# ADC_USB.net
KiCad netlist of a schematic drawn in Altium Designer
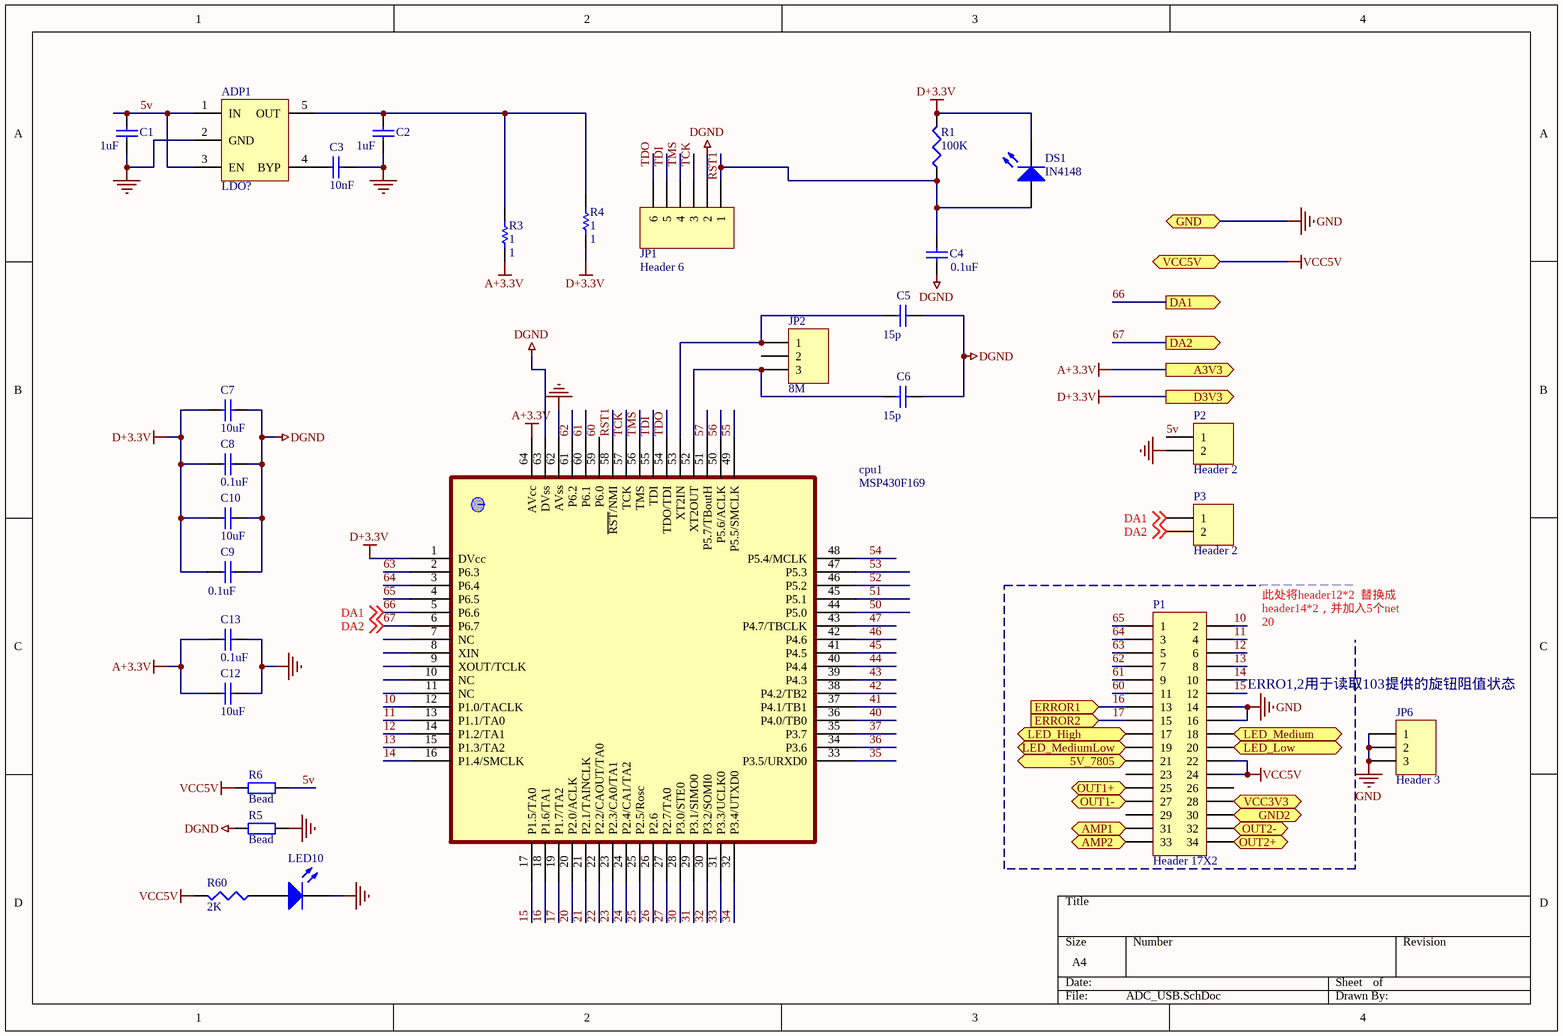
[diagram p0: ADC_USB.SchDoc]

(export (version "E")
  (design (tool "Eeschema 10.0.6"))
  (components
    (comp (ref "ADP1")
      (value "LDO?")
      (footprint "ADP1711_3v3")
      (libsource (lib "LDOlibrary") (part "ADP1711_3v3"))
    )
    (comp (ref "C1")
      (value "1uF")
      (footprint "CC1608-0603")
      (description "Capacitor (Semiconductor SIM Model)")
      (fields (field (name "Comment") "1u") (field (name "PUBLISHER") "Altium Limited"))
      (libsource (lib "Miscellaneous Devices") (part "Cap Semi"))
    )
    (comp (ref "C2")
      (value "1uF")
      (footprint "CC1608-0603")
      (description "Capacitor (Semiconductor SIM Model)")
      (fields (field (name "Comment") "1u") (field (name "PUBLISHER") "Altium Limited"))
      (libsource (lib "Miscellaneous Devices") (part "Cap Semi"))
    )
    (comp (ref "C3")
      (value "10nF")
      (footprint "CC1608-0603")
      (description "Capacitor (Semiconductor SIM Model)")
      (fields (field (name "Comment") "10n") (field (name "PUBLISHER") "Altium Limited"))
      (libsource (lib "Miscellaneous Devices") (part "Cap Semi"))
    )
    (comp (ref "C4")
      (value "0.1uF")
      (footprint "CC1608-0603")
      (description "Capacitor (Semiconductor SIM Model)")
      (fields (field (name "PUBLISHER") "Altium Limited"))
      (libsource (lib "LAN_server") (part "Cap Semi"))
    )
    (comp (ref "C5")
      (value "15p")
      (footprint "CC1608-0603")
      (description "Capacitor (Semiconductor SIM Model)")
      (fields (field (name "PUBLISHER") "Altium Limited"))
      (libsource (lib "LAN_server") (part "Cap Semi"))
    )
    (comp (ref "C6")
      (value "15p")
      (footprint "CC1608-0603")
      (description "Capacitor (Semiconductor SIM Model)")
      (fields (field (name "PUBLISHER") "Altium Limited"))
      (libsource (lib "LAN_server") (part "Cap Semi"))
    )
    (comp (ref "C7")
      (value "10uF")
      (footprint "CC3216-1206")
      (description "Capacitor (Semiconductor SIM Model)")
      (fields (field (name "PUBLISHER") "Altium Limited"))
      (libsource (lib "LAN_server") (part "Cap Semi"))
    )
    (comp (ref "C8")
      (value "0.1uF")
      (footprint "CC1608-0603")
      (description "Capacitor (Semiconductor SIM Model)")
      (fields (field (name "Comment") "Cap Semi") (field (name "PUBLISHER") "Altium Limited"))
      (libsource (lib "LAN_server") (part "Cap Semi"))
    )
    (comp (ref "C9")
      (value "0.1uF")
      (footprint "CC1608-0603")
      (description "Capacitor (Semiconductor SIM Model)")
      (fields (field (name "PUBLISHER") "Altium Limited"))
      (libsource (lib "LAN_server") (part "Cap Semi"))
    )
    (comp (ref "C10")
      (value "10uF")
      (footprint "CC3216-1206")
      (description "Capacitor (Semiconductor SIM Model)")
      (fields (field (name "PUBLISHER") "Altium Limited"))
      (libsource (lib "LAN_server") (part "Cap Semi"))
    )
    (comp (ref "C12")
      (value "10uF")
      (footprint "CC3216-1206")
      (description "Capacitor (Semiconductor SIM Model)")
      (fields (field (name "PUBLISHER") "Altium Limited"))
      (libsource (lib "LAN_server") (part "Cap Semi"))
    )
    (comp (ref "C13")
      (value "0.1uF")
      (footprint "CC1608-0603")
      (description "Capacitor (Semiconductor SIM Model)")
      (fields (field (name "PUBLISHER") "Altium Limited"))
      (libsource (lib "LAN_server") (part "Cap Semi"))
    )
    (comp (ref "cpu1")
      (value "MSP430F169")
      (footprint "msp430f149")
      (libsource (lib "msp430f149") (part "MSP430F149"))
    )
    (comp (ref "DS1")
      (value "IN4148")
      (footprint "SMD _LED")
      (description "Typical BLUE SiC LED")
      (fields (field (name "PUBLISHER") "Altium Limited"))
      (libsource (lib "Miscellaneous Devices") (part "LED3"))
    )
    (comp (ref "JP1")
      (value "Header 6")
      (footprint "HDR1X6")
      (description "Header, 6-Pin")
      (fields (field (name "PUBLISHER") "Altium Limited"))
      (libsource (lib "Miscellaneous Connectors") (part "Header 6"))
    )
    (comp (ref "JP2")
      (value "8M")
      (footprint "HDR1X3")
      (description "Header, 3-Pin")
      (fields (field (name "PUBLISHER") "Altium Limited"))
      (libsource (lib "Miscellaneous Connectors") (part "Header 3"))
    )
    (comp (ref "JP6")
      (value "Header 3")
      (footprint "HDR1X3")
      (description "Header, 3-Pin")
      (fields (field (name "PUBLISHER") "Altium Limited"))
      (libsource (lib "Miscellaneous Connectors") (part "Header 3"))
    )
    (comp (ref "LED10")
      (value "LED")
      (footprint "6-0805_M")
      (description "Typical BLUE SiC LED")
      (fields (field (name "PUBLISHER") "Altium Limited"))
      (libsource (lib "Miscellaneous Devices") (part "LED3"))
    )
    (comp (ref "P1")
      (value "Header 17X2")
      (footprint "HDR2X17-NIUJIAO")
      (description "Header, 17-Pin, Dual row")
      (fields (field (name "PUBLISHER") "Altium Limited"))
      (libsource (lib "Miscellaneous Connectors") (part "Header 17X2"))
    )
    (comp (ref "P2")
      (value "Header 2")
      (footprint "HDR1X2")
      (description "Header, 2-Pin")
      (fields (field (name "PUBLISHER") "Altium Limited"))
      (libsource (lib "Miscellaneous Connectors") (part "Header 2"))
    )
    (comp (ref "P3")
      (value "Header 2")
      (footprint "HDR1X2")
      (description "Header, 2-Pin")
      (fields (field (name "PUBLISHER") "Altium Limited"))
      (libsource (lib "Miscellaneous Connectors") (part "Header 2"))
    )
    (comp (ref "R1")
      (value "100K")
      (footprint "C1608-0603")
      (description "Resistor")
      (fields (field (name "PUBLISHER") "Altium Limited"))
      (libsource (lib "LAN_server") (part "Res3"))
    )
    (comp (ref "R3")
      (value "1")
      (footprint "6-0805_M")
      (description "Semiconductor Resistor")
      (fields (field (name "ALTIUM_VALUE") "1") (field (name "PUBLISHER") "Altium Limited"))
      (libsource (lib "Miscellaneous Devices") (part "Res Semi"))
    )
    (comp (ref "R4")
      (value "1")
      (footprint "6-0805_M")
      (description "Semiconductor Resistor")
      (fields (field (name "ALTIUM_VALUE") "1") (field (name "PUBLISHER") "Altium Limited"))
      (libsource (lib "Miscellaneous Devices") (part "Res Semi"))
    )
    (comp (ref "R5")
      (value "Bead")
      (footprint "6-0805_M")
      (description "Resistor")
      (fields (field (name "PUBLISHER") "Altium Limited"))
      (libsource (lib "") (part "Res2_1"))
    )
    (comp (ref "R6")
      (value "Bead")
      (footprint "6-0805_M")
      (description "Resistor")
      (fields (field (name "PUBLISHER") "Altium Limited"))
      (libsource (lib "Miscellaneous Devices") (part "Res2"))
    )
    (comp (ref "R60")
      (value "2K")
      (footprint "1608[0603]")
      (description "Resistor")
      (fields (field (name "PUBLISHER") "Altium Limited"))
      (libsource (lib "LAN_server") (part "Res3"))
    )
  )
  (nets
    (net (code "1") (name "/5V_7805") (class "Default")
      (node (ref "P1") (pin "21") (pinfunction "21_21") (pintype "passive"))
    )
    (net (code "2") (name "/5v") (class "Default")
      (node (ref "ADP1") (pin "1") (pinfunction "IN_1") (pintype "passive"))
      (node (ref "ADP1") (pin "3") (pinfunction "EN_3") (pintype "passive"))
      (node (ref "C1") (pin "1") (pinfunction "1_1") (pintype "passive"))
      (node (ref "P2") (pin "1") (pinfunction "1_1") (pintype "passive"))
      (node (ref "R6") (pin "1") (pinfunction "1_1") (pintype "passive"))
    )
    (net (code "3") (name "/10") (class "Default")
      (node (ref "P1") (pin "2") (pinfunction "2_2") (pintype "passive"))
      (node (ref "cpu1") (pin "12") (pinfunction "P1.0/TACLK_12") (pintype "passive"))
    )
    (net (code "4") (name "/11") (class "Default")
      (node (ref "P1") (pin "4") (pinfunction "4_4") (pintype "passive"))
      (node (ref "cpu1") (pin "13") (pinfunction "P1.1/TA0_13") (pintype "passive"))
    )
    (net (code "5") (name "/12") (class "Default")
      (node (ref "P1") (pin "6") (pinfunction "6_6") (pintype "passive"))
      (node (ref "cpu1") (pin "14") (pinfunction "P1.2/TA1_14") (pintype "passive"))
    )
    (net (code "6") (name "/13") (class "Default")
      (node (ref "P1") (pin "8") (pinfunction "8_8") (pintype "passive"))
      (node (ref "cpu1") (pin "15") (pinfunction "P1.3/TA2_15") (pintype "passive"))
    )
    (net (code "7") (name "/14") (class "Default")
      (node (ref "P1") (pin "10") (pinfunction "10_10") (pintype "passive"))
      (node (ref "cpu1") (pin "16") (pinfunction "P1.4/SMCLK_16") (pintype "passive"))
    )
    (net (code "8") (name "/15") (class "Default")
      (node (ref "P1") (pin "12") (pinfunction "12_12") (pintype "passive"))
      (node (ref "cpu1") (pin "17") (pinfunction "P1.5/TA0_17") (pintype "passive"))
    )
    (net (code "9") (name "/16") (class "Default")
      (node (ref "P1") (pin "13") (pinfunction "13_13") (pintype "passive"))
      (node (ref "cpu1") (pin "18") (pinfunction "P1.6/TA1_18") (pintype "passive"))
    )
    (net (code "10") (name "/17") (class "Default")
      (node (ref "P1") (pin "15") (pinfunction "15_15") (pintype "passive"))
      (node (ref "cpu1") (pin "19") (pinfunction "P1.7/TA2_19") (pintype "passive"))
    )
    (net (code "11") (name "/20") (class "Default")
      (node (ref "cpu1") (pin "20") (pinfunction "P2.0/ACLK_20") (pintype "passive"))
    )
    (net (code "12") (name "/21") (class "Default")
      (node (ref "cpu1") (pin "21") (pinfunction "P2.1/TAINCLK_21") (pintype "passive"))
    )
    (net (code "13") (name "/22") (class "Default")
      (node (ref "cpu1") (pin "22") (pinfunction "P2.2/CAOUT/TA0_22") (pintype "passive"))
    )
    (net (code "14") (name "/23") (class "Default")
      (node (ref "cpu1") (pin "23") (pinfunction "P2.3/CA0/TA1_23") (pintype "passive"))
    )
    (net (code "15") (name "/24") (class "Default")
      (node (ref "cpu1") (pin "24") (pinfunction "P2.4/CA1/TA2_24") (pintype "passive"))
    )
    (net (code "16") (name "/25") (class "Default")
      (node (ref "cpu1") (pin "25") (pinfunction "P2.5/Rosc_25") (pintype "passive"))
    )
    (net (code "17") (name "/26") (class "Default")
      (node (ref "cpu1") (pin "26") (pinfunction "P2.6_26") (pintype "passive"))
    )
    (net (code "18") (name "/27") (class "Default")
      (node (ref "cpu1") (pin "27") (pinfunction "P2.7/TA0_27") (pintype "passive"))
    )
    (net (code "19") (name "/30") (class "Default")
      (node (ref "cpu1") (pin "28") (pinfunction "P3.0/STE0_28") (pintype "passive"))
    )
    (net (code "20") (name "/31") (class "Default")
      (node (ref "cpu1") (pin "29") (pinfunction "P3.1/SIMO0_29") (pintype "passive"))
    )
    (net (code "21") (name "/32") (class "Default")
      (node (ref "cpu1") (pin "30") (pinfunction "P3.2/SOMI0_30") (pintype "passive"))
    )
    (net (code "22") (name "/33") (class "Default")
      (node (ref "cpu1") (pin "31") (pinfunction "P3.3/UCLK0_31") (pintype "passive"))
    )
    (net (code "23") (name "/34") (class "Default")
      (node (ref "cpu1") (pin "32") (pinfunction "P3.4/UTXD0_32") (pintype "passive"))
    )
    (net (code "24") (name "/35") (class "Default")
      (node (ref "cpu1") (pin "33") (pinfunction "P3.5/URXD0_33") (pintype "passive"))
    )
    (net (code "25") (name "/36") (class "Default")
      (node (ref "cpu1") (pin "34") (pinfunction "P3.6_34") (pintype "passive"))
    )
    (net (code "26") (name "/37") (class "Default")
      (node (ref "cpu1") (pin "35") (pinfunction "P3.7_35") (pintype "passive"))
    )
    (net (code "27") (name "/40") (class "Default")
      (node (ref "cpu1") (pin "36") (pinfunction "P4.0/TB0_36") (pintype "passive"))
    )
    (net (code "28") (name "/41") (class "Default")
      (node (ref "cpu1") (pin "37") (pinfunction "P4.1/TB1_37") (pintype "passive"))
    )
    (net (code "29") (name "/42") (class "Default")
      (node (ref "cpu1") (pin "38") (pinfunction "P4.2/TB2_38") (pintype "passive"))
    )
    (net (code "30") (name "/43") (class "Default")
      (node (ref "cpu1") (pin "39") (pinfunction "P4.3_39") (pintype "passive"))
    )
    (net (code "31") (name "/44") (class "Default")
      (node (ref "cpu1") (pin "40") (pinfunction "P4.4_40") (pintype "passive"))
    )
    (net (code "32") (name "/45") (class "Default")
      (node (ref "cpu1") (pin "41") (pinfunction "P4.5_41") (pintype "passive"))
    )
    (net (code "33") (name "/46") (class "Default")
      (node (ref "cpu1") (pin "42") (pinfunction "P4.6_42") (pintype "passive"))
    )
    (net (code "34") (name "/47") (class "Default")
      (node (ref "cpu1") (pin "43") (pinfunction "P4.7/TBCLK_43") (pintype "passive"))
    )
    (net (code "35") (name "/50") (class "Default")
      (node (ref "cpu1") (pin "44") (pinfunction "P5.0_44") (pintype "passive"))
    )
    (net (code "36") (name "/51") (class "Default")
      (node (ref "cpu1") (pin "45") (pinfunction "P5.1_45") (pintype "passive"))
    )
    (net (code "37") (name "/52") (class "Default")
      (node (ref "cpu1") (pin "46") (pinfunction "P5.2_46") (pintype "passive"))
    )
    (net (code "38") (name "/53") (class "Default")
      (node (ref "cpu1") (pin "47") (pinfunction "P5.3_47") (pintype "passive"))
    )
    (net (code "39") (name "/54") (class "Default")
      (node (ref "cpu1") (pin "48") (pinfunction "P5.4/MCLK_48") (pintype "passive"))
    )
    (net (code "40") (name "/55") (class "Default")
      (node (ref "cpu1") (pin "49") (pinfunction "P5.5/SMCLK_49") (pintype "passive"))
    )
    (net (code "41") (name "/56") (class "Default")
      (node (ref "cpu1") (pin "50") (pinfunction "P5.6/ACLK_50") (pintype "passive"))
    )
    (net (code "42") (name "/57") (class "Default")
      (node (ref "cpu1") (pin "51") (pinfunction "P5.7/TBoutH_51") (pintype "passive"))
    )
    (net (code "43") (name "/60") (class "Default")
      (node (ref "P1") (pin "11") (pinfunction "11_11") (pintype "passive"))
      (node (ref "cpu1") (pin "59") (pinfunction "P6.0_59") (pintype "passive"))
    )
    (net (code "44") (name "/61") (class "Default")
      (node (ref "P1") (pin "9") (pinfunction "9_9") (pintype "passive"))
      (node (ref "cpu1") (pin "60") (pinfunction "P6.1_60") (pintype "passive"))
    )
    (net (code "45") (name "/62") (class "Default")
      (node (ref "P1") (pin "7") (pinfunction "7_7") (pintype "passive"))
      (node (ref "cpu1") (pin "61") (pinfunction "P6.2_61") (pintype "passive"))
    )
    (net (code "46") (name "/63") (class "Default")
      (node (ref "P1") (pin "5") (pinfunction "5_5") (pintype "passive"))
      (node (ref "cpu1") (pin "2") (pinfunction "P6.3_2") (pintype "passive"))
    )
    (net (code "47") (name "/64") (class "Default")
      (node (ref "P1") (pin "3") (pinfunction "3_3") (pintype "passive"))
      (node (ref "cpu1") (pin "3") (pinfunction "P6.4_3") (pintype "passive"))
    )
    (net (code "48") (name "/65") (class "Default")
      (node (ref "P1") (pin "1") (pinfunction "1_1") (pintype "passive"))
      (node (ref "cpu1") (pin "4") (pinfunction "P6.5_4") (pintype "passive"))
    )
    (net (code "49") (name "/AMP1") (class "Default")
      (node (ref "P1") (pin "31") (pinfunction "31_31") (pintype "passive"))
    )
    (net (code "50") (name "/AMP2") (class "Default")
      (node (ref "P1") (pin "33") (pinfunction "33_33") (pintype "passive"))
    )
    (net (code "51") (name "/GND2") (class "Default")
      (node (ref "P1") (pin "30") (pinfunction "30_30") (pintype "passive"))
    )
    (net (code "52") (name "/LED_High") (class "Default")
      (node (ref "P1") (pin "17") (pinfunction "17_17") (pintype "passive"))
    )
    (net (code "53") (name "/LED_Low") (class "Default")
      (node (ref "P1") (pin "20") (pinfunction "20_20") (pintype "passive"))
    )
    (net (code "54") (name "/LED_Medium") (class "Default")
      (node (ref "P1") (pin "18") (pinfunction "18_18") (pintype "passive"))
    )
    (net (code "55") (name "/LED_MediumLow") (class "Default")
      (node (ref "P1") (pin "19") (pinfunction "19_19") (pintype "passive"))
    )
    (net (code "56") (name "/OUT1+") (class "Default")
      (node (ref "P1") (pin "25") (pinfunction "25_25") (pintype "passive"))
    )
    (net (code "57") (name "/OUT1-") (class "Default")
      (node (ref "P1") (pin "27") (pinfunction "27_27") (pintype "passive"))
    )
    (net (code "58") (name "/OUT2+") (class "Default")
      (node (ref "P1") (pin "34") (pinfunction "34_34") (pintype "passive"))
    )
    (net (code "59") (name "/OUT2-") (class "Default")
      (node (ref "P1") (pin "32") (pinfunction "32_32") (pintype "passive"))
    )
    (net (code "60") (name "/RST1") (class "Default")
      (node (ref "C4") (pin "2") (pinfunction "2_2") (pintype "passive"))
      (node (ref "DS1") (pin "1") (pinfunction "A_1") (pintype "passive"))
      (node (ref "JP1") (pin "1") (pinfunction "1_1") (pintype "passive"))
      (node (ref "R1") (pin "1") (pinfunction "1_1") (pintype "passive"))
      (node (ref "cpu1") (pin "58") (pinfunction "~{RST}/NMI_58") (pintype "passive"))
    )
    (net (code "61") (name "/TCK") (class "Default")
      (node (ref "JP1") (pin "3") (pinfunction "3_3") (pintype "passive"))
      (node (ref "cpu1") (pin "57") (pinfunction "TCK_57") (pintype "passive"))
    )
    (net (code "62") (name "/TDI") (class "Default")
      (node (ref "JP1") (pin "5") (pinfunction "5_5") (pintype "passive"))
      (node (ref "cpu1") (pin "55") (pinfunction "TDI_55") (pintype "passive"))
    )
    (net (code "63") (name "/TDO") (class "Default")
      (node (ref "JP1") (pin "6") (pinfunction "6_6") (pintype "passive"))
      (node (ref "cpu1") (pin "54") (pinfunction "TDO/TDI_54") (pintype "passive"))
    )
    (net (code "64") (name "/TMS") (class "Default")
      (node (ref "JP1") (pin "4") (pinfunction "4_4") (pintype "passive"))
      (node (ref "cpu1") (pin "56") (pinfunction "TMS_56") (pintype "passive"))
    )
    (net (code "65") (name "/VCC3V3") (class "Default")
      (node (ref "P1") (pin "28") (pinfunction "28_28") (pintype "passive"))
    )
    (net (code "66") (name "A+3.3V") (class "Default")
      (node (ref "C12") (pin "2") (pinfunction "2_2") (pintype "passive"))
      (node (ref "C13") (pin "2") (pinfunction "2_2") (pintype "passive"))
      (node (ref "R3") (pin "1") (pinfunction "1_1") (pintype "passive"))
      (node (ref "cpu1") (pin "64") (pinfunction "AVcc_64") (pintype "passive"))
    )
    (net (code "67") (name "D+3.3V") (class "Default")
      (node (ref "C10") (pin "2") (pinfunction "2_2") (pintype "passive"))
      (node (ref "C7") (pin "2") (pinfunction "2_2") (pintype "passive"))
      (node (ref "C8") (pin "2") (pinfunction "2_2") (pintype "passive"))
      (node (ref "C9") (pin "2") (pinfunction "2_2") (pintype "passive"))
      (node (ref "DS1") (pin "2") (pinfunction "K_2") (pintype "passive"))
      (node (ref "R1") (pin "2") (pinfunction "2_2") (pintype "passive"))
      (node (ref "R4") (pin "1") (pinfunction "1_1") (pintype "passive"))
      (node (ref "cpu1") (pin "1") (pinfunction "DVcc_1") (pintype "passive"))
    )
    (net (code "68") (name "DA1") (class "Default")
      (node (ref "P3") (pin "1") (pinfunction "1_1") (pintype "passive"))
      (node (ref "cpu1") (pin "5") (pinfunction "P6.6_5") (pintype "passive"))
    )
    (net (code "69") (name "DA2") (class "Default")
      (node (ref "P3") (pin "2") (pinfunction "2_2") (pintype "passive"))
      (node (ref "cpu1") (pin "6") (pinfunction "P6.7_6") (pintype "passive"))
    )
    (net (code "70") (name "DGND") (class "Default")
      (node (ref "C10") (pin "1") (pinfunction "1_1") (pintype "passive"))
      (node (ref "C4") (pin "1") (pinfunction "1_1") (pintype "passive"))
      (node (ref "C5") (pin "1") (pinfunction "1_1") (pintype "passive"))
      (node (ref "C6") (pin "1") (pinfunction "1_1") (pintype "passive"))
      (node (ref "C7") (pin "1") (pinfunction "1_1") (pintype "passive"))
      (node (ref "C8") (pin "1") (pinfunction "1_1") (pintype "passive"))
      (node (ref "C9") (pin "1") (pinfunction "1_1") (pintype "passive"))
      (node (ref "JP1") (pin "2") (pinfunction "2_2") (pintype "passive"))
      (node (ref "R5") (pin "1") (pinfunction "1_1") (pintype "passive"))
      (node (ref "cpu1") (pin "63") (pinfunction "DVss_63") (pintype "passive"))
    )
    (net (code "71") (name "GND") (class "Default")
      (node (ref "ADP1") (pin "2") (pinfunction "GND_2") (pintype "passive"))
      (node (ref "C1") (pin "2") (pinfunction "2_2") (pintype "passive"))
      (node (ref "C12") (pin "1") (pinfunction "1_1") (pintype "passive"))
      (node (ref "C13") (pin "1") (pinfunction "1_1") (pintype "passive"))
      (node (ref "C2") (pin "2") (pinfunction "2_2") (pintype "passive"))
      (node (ref "C3") (pin "2") (pinfunction "2_2") (pintype "passive"))
      (node (ref "JP6") (pin "1") (pinfunction "1_1") (pintype "passive"))
      (node (ref "JP6") (pin "2") (pinfunction "2_2") (pintype "passive"))
      (node (ref "JP6") (pin "3") (pinfunction "3_3") (pintype "passive"))
      (node (ref "LED10") (pin "2") (pinfunction "K_2") (pintype "passive"))
      (node (ref "P1") (pin "14") (pinfunction "14_14") (pintype "passive"))
      (node (ref "P1") (pin "16") (pinfunction "16_16") (pintype "passive"))
      (node (ref "P2") (pin "2") (pinfunction "2_2") (pintype "passive"))
      (node (ref "R5") (pin "2") (pinfunction "2_2") (pintype "passive"))
      (node (ref "cpu1") (pin "62") (pinfunction "AVss_62") (pintype "passive"))
    )
    (net (code "72") (name "Net-(ADP1-BYP)") (class "Default")
      (node (ref "ADP1") (pin "4") (pinfunction "BYP_4") (pintype "passive"))
      (node (ref "C3") (pin "1") (pinfunction "1_1") (pintype "passive"))
    )
    (net (code "73") (name "Net-(ADP1-OUT)") (class "Default")
      (node (ref "ADP1") (pin "5") (pinfunction "OUT_5") (pintype "passive"))
      (node (ref "C2") (pin "1") (pinfunction "1_1") (pintype "passive"))
      (node (ref "R3") (pin "2") (pinfunction "2_2") (pintype "passive"))
      (node (ref "R4") (pin "2") (pinfunction "2_2") (pintype "passive"))
    )
    (net (code "74") (name "Net-(LED10-A)") (class "Default")
      (node (ref "LED10") (pin "1") (pinfunction "A_1") (pintype "passive"))
      (node (ref "R60") (pin "1") (pinfunction "1_1") (pintype "passive"))
    )
    (net (code "75") (name "Net-(cpu1-XT2IN)") (class "Default")
      (node (ref "C5") (pin "2") (pinfunction "2_2") (pintype "passive"))
      (node (ref "JP2") (pin "1") (pinfunction "1_1") (pintype "passive"))
      (node (ref "cpu1") (pin "53") (pinfunction "XT2IN_53") (pintype "passive"))
    )
    (net (code "76") (name "Net-(cpu1-XT2OUT)") (class "Default")
      (node (ref "C6") (pin "2") (pinfunction "2_2") (pintype "passive"))
      (node (ref "JP2") (pin "3") (pinfunction "3_3") (pintype "passive"))
      (node (ref "cpu1") (pin "52") (pinfunction "XT2OUT_52") (pintype "passive"))
    )
    (net (code "77") (name "VCC5V") (class "Default")
      (node (ref "P1") (pin "22") (pinfunction "22_22") (pintype "passive"))
      (node (ref "P1") (pin "24") (pinfunction "24_24") (pintype "passive"))
      (node (ref "R6") (pin "2") (pinfunction "2_2") (pintype "passive"))
      (node (ref "R60") (pin "2") (pinfunction "2_2") (pintype "passive"))
    )
    (net (code "78") (name "unconnected-(JP2-Pad2)") (class "Default")
      (node (ref "JP2") (pin "2") (pinfunction "2_2") (pintype "passive"))
    )
    (net (code "79") (name "unconnected-(P1-Pad23)") (class "Default")
      (node (ref "P1") (pin "23") (pinfunction "23_23") (pintype "passive"))
    )
    (net (code "80") (name "unconnected-(P1-Pad26)") (class "Default")
      (node (ref "P1") (pin "26") (pinfunction "26_26") (pintype "passive"))
    )
    (net (code "81") (name "unconnected-(P1-Pad29)") (class "Default")
      (node (ref "P1") (pin "29") (pinfunction "29_29") (pintype "passive"))
    )
    (net (code "82") (name "unconnected-(cpu1-NC-Pad7)") (class "Default")
      (node (ref "cpu1") (pin "7") (pinfunction "NC_7") (pintype "passive"))
    )
    (net (code "83") (name "unconnected-(cpu1-NC-Pad10)") (class "Default")
      (node (ref "cpu1") (pin "10") (pinfunction "NC_10") (pintype "passive"))
    )
    (net (code "84") (name "unconnected-(cpu1-NC-Pad11)") (class "Default")
      (node (ref "cpu1") (pin "11") (pinfunction "NC_11") (pintype "passive"))
    )
    (net (code "85") (name "unconnected-(cpu1-XIN-Pad8)") (class "Default")
      (node (ref "cpu1") (pin "8") (pinfunction "XIN_8") (pintype "passive"))
    )
    (net (code "86") (name "unconnected-(cpu1-XOUT{slash}TCLK-Pad9)") (class "Default")
      (node (ref "cpu1") (pin "9") (pinfunction "XOUT/TCLK_9") (pintype "passive"))
    )
  )
)
